# Skema_Seven_Segment.net
KiCad netlist of a schematic drawn in Altium Designer
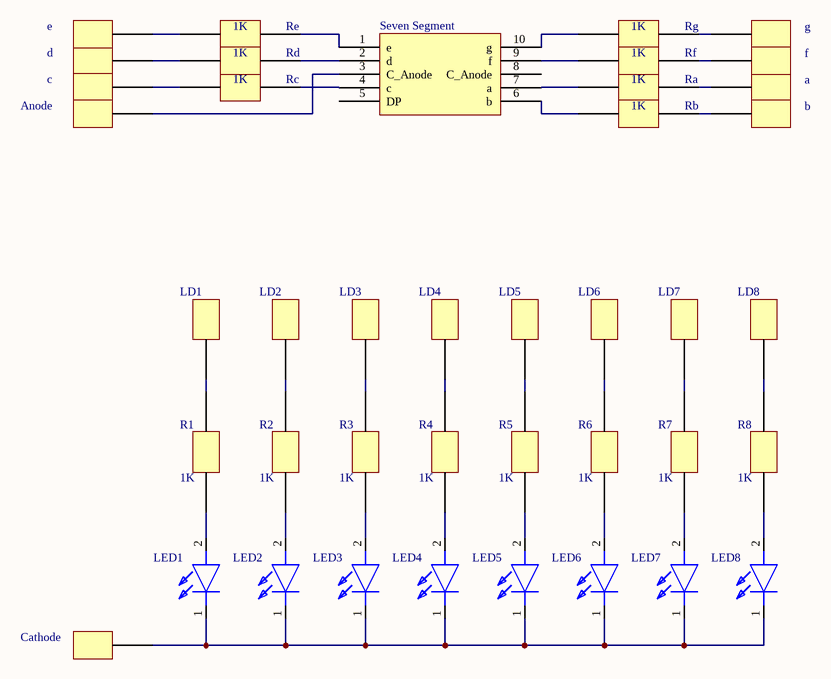
[diagram p0: Skema Seven Segment.SchDoc]

(export (version "E")
  (design (tool "Eeschema 10.0.6"))
  (components
    (comp (ref "a")
      (value "Female_Connector_Banana")
      (footprint "F_Banana")
      (libsource (lib "") (part "Female_Connector_Banana_2"))
    )
    (comp (ref "Anode")
      (value "Female_Connector_Banana")
      (footprint "F_Banana")
      (libsource (lib "") (part "Female_Connector_Banana_1"))
    )
    (comp (ref "b")
      (value "Female_Connector_Banana")
      (footprint "F_Banana")
      (libsource (lib "") (part "Female_Connector_Banana_2"))
    )
    (comp (ref "c")
      (value "Female_Connector_Banana")
      (footprint "F_Banana")
      (libsource (lib "") (part "Female_Connector_Banana_1"))
    )
    (comp (ref "Cathode")
      (value "Female_Connector_Banana")
      (footprint "F_Banana")
      (libsource (lib "") (part "Female_Connector_Banana_1"))
    )
    (comp (ref "d")
      (value "Female_Connector_Banana")
      (footprint "F_Banana")
      (libsource (lib "") (part "Female_Connector_Banana_1"))
    )
    (comp (ref "e")
      (value "Female_Connector_Banana")
      (footprint "F_Banana")
      (libsource (lib "") (part "Female_Connector_Banana_1"))
    )
    (comp (ref "f")
      (value "Female_Connector_Banana")
      (footprint "F_Banana")
      (libsource (lib "") (part "Female_Connector_Banana_2"))
    )
    (comp (ref "g")
      (value "Female_Connector_Banana")
      (footprint "F_Banana")
      (libsource (lib "") (part "Female_Connector_Banana_2"))
    )
    (comp (ref "LD1")
      (value "Female_Connector_Banana")
      (footprint "F_Banana")
      (libsource (lib "SamacSys") (part "Female_Connector_Banana"))
    )
    (comp (ref "LD2")
      (value "Female_Connector_Banana")
      (footprint "F_Banana")
      (libsource (lib "SamacSys") (part "Female_Connector_Banana"))
    )
    (comp (ref "LD3")
      (value "Female_Connector_Banana")
      (footprint "F_Banana")
      (libsource (lib "SamacSys") (part "Female_Connector_Banana"))
    )
    (comp (ref "LD4")
      (value "Female_Connector_Banana")
      (footprint "F_Banana")
      (libsource (lib "SamacSys") (part "Female_Connector_Banana"))
    )
    (comp (ref "LD5")
      (value "Female_Connector_Banana")
      (footprint "F_Banana")
      (libsource (lib "SamacSys") (part "Female_Connector_Banana"))
    )
    (comp (ref "LD6")
      (value "Female_Connector_Banana")
      (footprint "F_Banana")
      (libsource (lib "SamacSys") (part "Female_Connector_Banana"))
    )
    (comp (ref "LD7")
      (value "Female_Connector_Banana")
      (footprint "F_Banana")
      (libsource (lib "SamacSys") (part "Female_Connector_Banana"))
    )
    (comp (ref "LD8")
      (value "Female_Connector_Banana")
      (footprint "F_Banana")
      (libsource (lib "SamacSys") (part "Female_Connector_Banana"))
    )
    (comp (ref "LED1")
      (value "228-5045")
      (footprint "SamacSys:2285045")
      (description "LED")
      (libsource (lib "SamacSys") (part "228-5045"))
    )
    (comp (ref "LED2")
      (value "228-5045")
      (footprint "SamacSys:2285045")
      (description "LED")
      (libsource (lib "SamacSys") (part "228-5045"))
    )
    (comp (ref "LED3")
      (value "228-5045")
      (footprint "SamacSys:2285045")
      (description "LED")
      (libsource (lib "SamacSys") (part "228-5045"))
    )
    (comp (ref "LED4")
      (value "228-5045")
      (footprint "SamacSys:2285045")
      (description "LED")
      (libsource (lib "SamacSys") (part "228-5045"))
    )
    (comp (ref "LED5")
      (value "228-5045")
      (footprint "SamacSys:2285045")
      (description "LED")
      (libsource (lib "SamacSys") (part "228-5045"))
    )
    (comp (ref "LED6")
      (value "228-5045")
      (footprint "SamacSys:2285045")
      (description "LED")
      (libsource (lib "SamacSys") (part "228-5045"))
    )
    (comp (ref "LED7")
      (value "228-5045")
      (footprint "SamacSys:2285045")
      (description "LED")
      (libsource (lib "SamacSys") (part "228-5045"))
    )
    (comp (ref "LED8")
      (value "228-5045")
      (footprint "SamacSys:2285045")
      (description "LED")
      (libsource (lib "SamacSys") (part "228-5045"))
    )
    (comp (ref "R1")
      (value "1K")
      (footprint "Resistor")
      (description "Fixed Resistance")
      (libsource (lib "Header") (part "Resistor"))
    )
    (comp (ref "R2")
      (value "1K")
      (footprint "Resistor")
      (description "Fixed Resistance")
      (libsource (lib "Header") (part "Resistor"))
    )
    (comp (ref "R3")
      (value "1K")
      (footprint "Resistor")
      (description "Fixed Resistance")
      (libsource (lib "Header") (part "Resistor"))
    )
    (comp (ref "R4")
      (value "1K")
      (footprint "Resistor")
      (description "Fixed Resistance")
      (libsource (lib "Header") (part "Resistor"))
    )
    (comp (ref "R5")
      (value "1K")
      (footprint "Resistor")
      (description "Fixed Resistance")
      (libsource (lib "Header") (part "Resistor"))
    )
    (comp (ref "R6")
      (value "1K")
      (footprint "Resistor")
      (description "Fixed Resistance")
      (libsource (lib "Header") (part "Resistor"))
    )
    (comp (ref "R7")
      (value "1K")
      (footprint "Resistor")
      (description "Fixed Resistance")
      (libsource (lib "Header") (part "Resistor"))
    )
    (comp (ref "R8")
      (value "1K")
      (footprint "Resistor")
      (description "Fixed Resistance")
      (libsource (lib "Header") (part "Resistor"))
    )
    (comp (ref "Ra")
      (value "1K")
      (footprint "Resistor")
      (description "Fixed Resistance")
      (libsource (lib "") (part "Resistor_1"))
    )
    (comp (ref "Rb")
      (value "1K")
      (footprint "Resistor")
      (description "Fixed Resistance")
      (libsource (lib "") (part "Resistor_1"))
    )
    (comp (ref "Rc")
      (value "1K")
      (footprint "Resistor")
      (description "Fixed Resistance")
      (libsource (lib "") (part "Resistor_1"))
    )
    (comp (ref "Rd")
      (value "1K")
      (footprint "Resistor")
      (description "Fixed Resistance")
      (libsource (lib "") (part "Resistor_1"))
    )
    (comp (ref "Re")
      (value "1K")
      (footprint "Resistor")
      (description "Fixed Resistance")
      (libsource (lib "") (part "Resistor_1"))
    )
    (comp (ref "Rf")
      (value "1K")
      (footprint "Resistor")
      (description "Fixed Resistance")
      (libsource (lib "") (part "Resistor_1"))
    )
    (comp (ref "Rg")
      (value "1K")
      (footprint "Resistor")
      (description "Fixed Resistance")
      (libsource (lib "") (part "Resistor_1"))
    )
    (comp (ref "Seven Segment")
      (value "5161AS-Seven-Segment")
      (footprint "5161AS-Seven-Segment")
      (libsource (lib "Header") (part "5161AS-Seven-Segment"))
    )
  )
  (nets
    (net (code "1") (name "Net-(Anode-IO)") (class "Default")
      (node (ref "Anode") (pin "1") (pinfunction "IO_1") (pintype "passive"))
      (node (ref "Seven Segment") (pin "3") (pinfunction "C_Anode_3") (pintype "passive"))
    )
    (net (code "2") (name "Net-(Cathode-IO)") (class "Default")
      (node (ref "Cathode") (pin "1") (pinfunction "IO_1") (pintype "passive"))
      (node (ref "LED1") (pin "1") (pinfunction "K_1") (pintype "passive"))
      (node (ref "LED2") (pin "1") (pinfunction "K_1") (pintype "passive"))
      (node (ref "LED3") (pin "1") (pinfunction "K_1") (pintype "passive"))
      (node (ref "LED4") (pin "1") (pinfunction "K_1") (pintype "passive"))
      (node (ref "LED5") (pin "1") (pinfunction "K_1") (pintype "passive"))
      (node (ref "LED6") (pin "1") (pinfunction "K_1") (pintype "passive"))
      (node (ref "LED7") (pin "1") (pinfunction "K_1") (pintype "passive"))
      (node (ref "LED8") (pin "1") (pinfunction "K_1") (pintype "passive"))
    )
    (net (code "3") (name "Net-(LD1-IO)") (class "Default")
      (node (ref "LD1") (pin "1") (pinfunction "IO_1") (pintype "passive"))
      (node (ref "R1") (pin "2") (pinfunction "2_2") (pintype "passive"))
    )
    (net (code "4") (name "Net-(LD2-IO)") (class "Default")
      (node (ref "LD2") (pin "1") (pinfunction "IO_1") (pintype "passive"))
      (node (ref "R2") (pin "2") (pinfunction "2_2") (pintype "passive"))
    )
    (net (code "5") (name "Net-(LD3-IO)") (class "Default")
      (node (ref "LD3") (pin "1") (pinfunction "IO_1") (pintype "passive"))
      (node (ref "R3") (pin "2") (pinfunction "2_2") (pintype "passive"))
    )
    (net (code "6") (name "Net-(LD4-IO)") (class "Default")
      (node (ref "LD4") (pin "1") (pinfunction "IO_1") (pintype "passive"))
      (node (ref "R4") (pin "2") (pinfunction "2_2") (pintype "passive"))
    )
    (net (code "7") (name "Net-(LD5-IO)") (class "Default")
      (node (ref "LD5") (pin "1") (pinfunction "IO_1") (pintype "passive"))
      (node (ref "R5") (pin "2") (pinfunction "2_2") (pintype "passive"))
    )
    (net (code "8") (name "Net-(LD6-IO)") (class "Default")
      (node (ref "LD6") (pin "1") (pinfunction "IO_1") (pintype "passive"))
      (node (ref "R6") (pin "2") (pinfunction "2_2") (pintype "passive"))
    )
    (net (code "9") (name "Net-(LD7-IO)") (class "Default")
      (node (ref "LD7") (pin "1") (pinfunction "IO_1") (pintype "passive"))
      (node (ref "R7") (pin "2") (pinfunction "2_2") (pintype "passive"))
    )
    (net (code "10") (name "Net-(LD8-IO)") (class "Default")
      (node (ref "LD8") (pin "1") (pinfunction "IO_1") (pintype "passive"))
      (node (ref "R8") (pin "2") (pinfunction "2_2") (pintype "passive"))
    )
    (net (code "11") (name "Net-(LED1-A)") (class "Default")
      (node (ref "LED1") (pin "2") (pinfunction "A_2") (pintype "passive"))
      (node (ref "R1") (pin "1") (pinfunction "1_1") (pintype "passive"))
    )
    (net (code "12") (name "Net-(LED2-A)") (class "Default")
      (node (ref "LED2") (pin "2") (pinfunction "A_2") (pintype "passive"))
      (node (ref "R2") (pin "1") (pinfunction "1_1") (pintype "passive"))
    )
    (net (code "13") (name "Net-(LED3-A)") (class "Default")
      (node (ref "LED3") (pin "2") (pinfunction "A_2") (pintype "passive"))
      (node (ref "R3") (pin "1") (pinfunction "1_1") (pintype "passive"))
    )
    (net (code "14") (name "Net-(LED4-A)") (class "Default")
      (node (ref "LED4") (pin "2") (pinfunction "A_2") (pintype "passive"))
      (node (ref "R4") (pin "1") (pinfunction "1_1") (pintype "passive"))
    )
    (net (code "15") (name "Net-(LED5-A)") (class "Default")
      (node (ref "LED5") (pin "2") (pinfunction "A_2") (pintype "passive"))
      (node (ref "R5") (pin "1") (pinfunction "1_1") (pintype "passive"))
    )
    (net (code "16") (name "Net-(LED6-A)") (class "Default")
      (node (ref "LED6") (pin "2") (pinfunction "A_2") (pintype "passive"))
      (node (ref "R6") (pin "1") (pinfunction "1_1") (pintype "passive"))
    )
    (net (code "17") (name "Net-(LED7-A)") (class "Default")
      (node (ref "LED7") (pin "2") (pinfunction "A_2") (pintype "passive"))
      (node (ref "R7") (pin "1") (pinfunction "1_1") (pintype "passive"))
    )
    (net (code "18") (name "Net-(LED8-A)") (class "Default")
      (node (ref "LED8") (pin "2") (pinfunction "A_2") (pintype "passive"))
      (node (ref "R8") (pin "1") (pinfunction "1_1") (pintype "passive"))
    )
    (net (code "19") (name "Net-(Seven Segment-a)") (class "Default")
      (node (ref "Ra") (pin "1") (pinfunction "1_1") (pintype "passive"))
      (node (ref "Seven Segment") (pin "7") (pinfunction "a_7") (pintype "passive"))
    )
    (net (code "20") (name "Net-(Seven Segment-b)") (class "Default")
      (node (ref "Rb") (pin "1") (pinfunction "1_1") (pintype "passive"))
      (node (ref "Seven Segment") (pin "6") (pinfunction "b_6") (pintype "passive"))
    )
    (net (code "21") (name "Net-(Seven Segment-c)") (class "Default")
      (node (ref "Rc") (pin "2") (pinfunction "2_2") (pintype "passive"))
      (node (ref "Seven Segment") (pin "4") (pinfunction "c_4") (pintype "passive"))
    )
    (net (code "22") (name "Net-(Seven Segment-d)") (class "Default")
      (node (ref "Rd") (pin "2") (pinfunction "2_2") (pintype "passive"))
      (node (ref "Seven Segment") (pin "2") (pinfunction "d_2") (pintype "passive"))
    )
    (net (code "23") (name "Net-(Seven Segment-e)") (class "Default")
      (node (ref "Re") (pin "2") (pinfunction "2_2") (pintype "passive"))
      (node (ref "Seven Segment") (pin "1") (pinfunction "e_1") (pintype "passive"))
    )
    (net (code "24") (name "Net-(Seven Segment-f)") (class "Default")
      (node (ref "Rf") (pin "1") (pinfunction "1_1") (pintype "passive"))
      (node (ref "Seven Segment") (pin "9") (pinfunction "f_9") (pintype "passive"))
    )
    (net (code "25") (name "Net-(Seven Segment-g)") (class "Default")
      (node (ref "Rg") (pin "1") (pinfunction "1_1") (pintype "passive"))
      (node (ref "Seven Segment") (pin "10") (pinfunction "g_10") (pintype "passive"))
    )
    (net (code "26") (name "Net-(a-IO)") (class "Default")
      (node (ref "Ra") (pin "2") (pinfunction "2_2") (pintype "passive"))
      (node (ref "a") (pin "1") (pinfunction "IO_1") (pintype "passive"))
    )
    (net (code "27") (name "Net-(b-IO)") (class "Default")
      (node (ref "Rb") (pin "2") (pinfunction "2_2") (pintype "passive"))
      (node (ref "b") (pin "1") (pinfunction "IO_1") (pintype "passive"))
    )
    (net (code "28") (name "Net-(c-IO)") (class "Default")
      (node (ref "Rc") (pin "1") (pinfunction "1_1") (pintype "passive"))
      (node (ref "c") (pin "1") (pinfunction "IO_1") (pintype "passive"))
    )
    (net (code "29") (name "Net-(d-IO)") (class "Default")
      (node (ref "Rd") (pin "1") (pinfunction "1_1") (pintype "passive"))
      (node (ref "d") (pin "1") (pinfunction "IO_1") (pintype "passive"))
    )
    (net (code "30") (name "Net-(e-IO)") (class "Default")
      (node (ref "Re") (pin "1") (pinfunction "1_1") (pintype "passive"))
      (node (ref "e") (pin "1") (pinfunction "IO_1") (pintype "passive"))
    )
    (net (code "31") (name "Net-(f-IO)") (class "Default")
      (node (ref "Rf") (pin "2") (pinfunction "2_2") (pintype "passive"))
      (node (ref "f") (pin "1") (pinfunction "IO_1") (pintype "passive"))
    )
    (net (code "32") (name "Net-(g-IO)") (class "Default")
      (node (ref "Rg") (pin "2") (pinfunction "2_2") (pintype "passive"))
      (node (ref "g") (pin "1") (pinfunction "IO_1") (pintype "passive"))
    )
    (net (code "33") (name "unconnected-(Seven Segment-C_Anode-Pad8)") (class "Default")
      (node (ref "Seven Segment") (pin "8") (pinfunction "C_Anode_8") (pintype "passive"))
    )
    (net (code "34") (name "unconnected-(Seven Segment-DP-Pad5)") (class "Default")
      (node (ref "Seven Segment") (pin "5") (pinfunction "DP_5") (pintype "passive"))
    )
  )
)
